# working.net
KiCad netlist of a schematic drawn in EAGLE
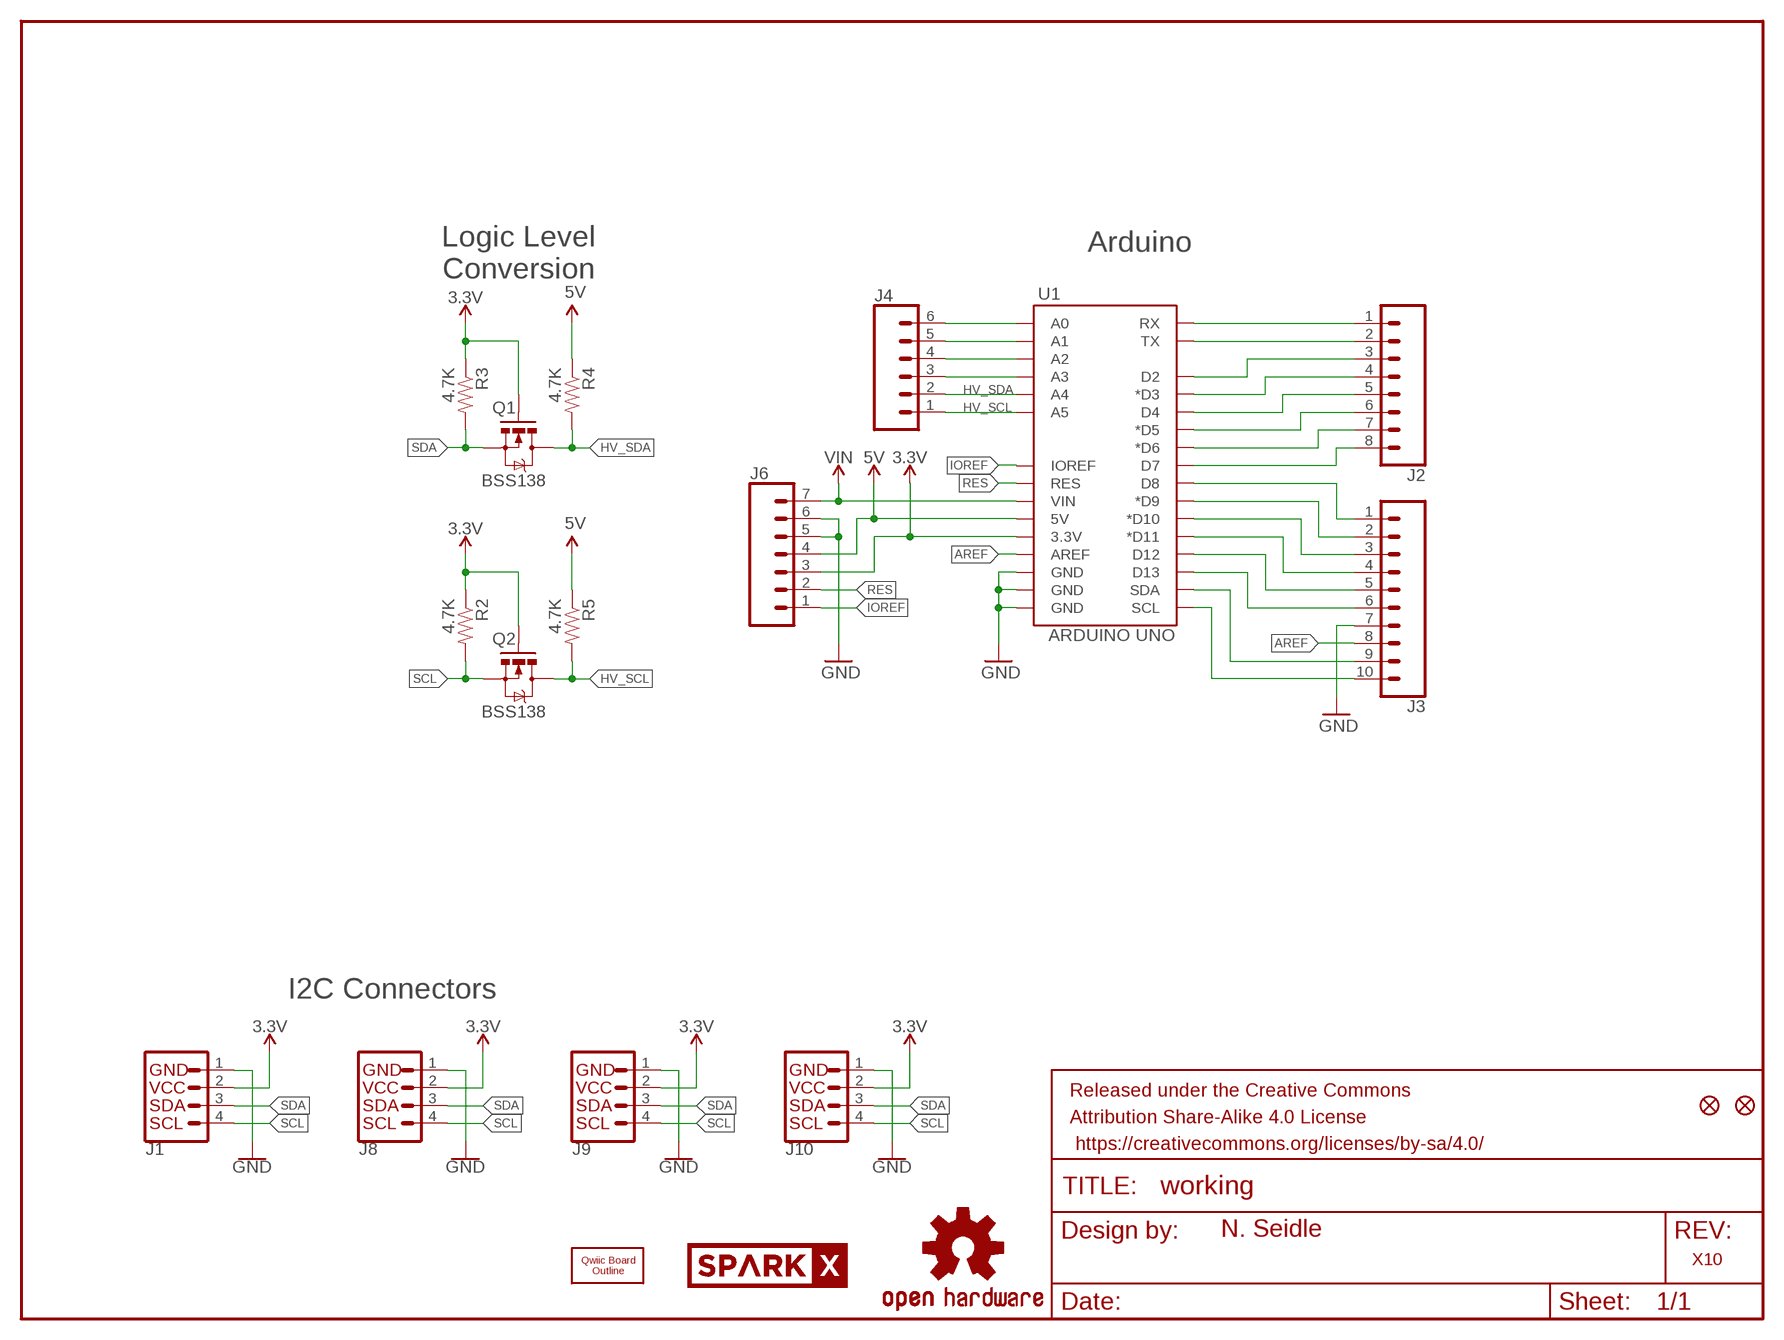
[diagram p0: schematic, sheet 1]

(export (version "E")
  (design (tool "Eeschema 10.0.6"))
  (components
    (comp (ref "FD1")
      (value "FIDUCIAL1X2")
      (footprint "eagle-import:FIDUCIAL-1X2")
      (libsource (lib "eagle-import") (part "FIDUCIAL1X2"))
    )
    (comp (ref "FD2")
      (value "FIDUCIAL1X2")
      (footprint "eagle-import:FIDUCIAL-1X2")
      (libsource (lib "eagle-import") (part "FIDUCIAL1X2"))
    )
    (comp (ref "FRAME1")
      (value "FRAME-LETTER")
      (footprint "eagle-import:CREATIVE_COMMONS")
      (libsource (lib "eagle-import") (part "FRAME-LETTER"))
    )
    (comp (ref "J1")
      (value "I2C_STANDARDJS-1MM")
      (footprint "eagle-import:1X04_1MM_RA")
      (libsource (lib "eagle-import") (part "I2C_STANDARDJS-1MM"))
    )
    (comp (ref "J2")
      (value "CONN_08NO_SILK_FEMALE_PTH")
      (footprint "eagle-import:1X08_NO_SILK")
      (libsource (lib "eagle-import") (part "CONN_08NO_SILK_FEMALE_PTH"))
    )
    (comp (ref "J3")
      (value "CONN_10NO_SILK_PTH_FEMALE")
      (footprint "eagle-import:1X10_NO_SILK")
      (libsource (lib "eagle-import") (part "CONN_10NO_SILK_PTH_FEMALE"))
    )
    (comp (ref "J4")
      (value "CONN_06NO_SILK_FEMALE_PTH")
      (footprint "eagle-import:1X06_NO_SILK")
      (libsource (lib "eagle-import") (part "CONN_06NO_SILK_FEMALE_PTH"))
    )
    (comp (ref "J6")
      (value "CONN_07NO_SILK")
      (footprint "eagle-import:1X07_NO_SILK")
      (libsource (lib "eagle-import") (part "CONN_07NO_SILK"))
    )
    (comp (ref "J8")
      (value "I2C_STANDARDJS-1MM")
      (footprint "eagle-import:1X04_1MM_RA")
      (libsource (lib "eagle-import") (part "I2C_STANDARDJS-1MM"))
    )
    (comp (ref "J9")
      (value "I2C_STANDARDJS-1MM")
      (footprint "eagle-import:1X04_1MM_RA")
      (libsource (lib "eagle-import") (part "I2C_STANDARDJS-1MM"))
    )
    (comp (ref "J10")
      (value "I2C_STANDARDJS-1MM")
      (footprint "eagle-import:1X04_1MM_RA")
      (libsource (lib "eagle-import") (part "I2C_STANDARDJS-1MM"))
    )
    (comp (ref "LOGO1")
      (value "OSHW-LOGOMINI")
      (footprint "eagle-import:OSHW-LOGO-MINI")
      (libsource (lib "eagle-import") (part "OSHW-LOGOMINI"))
    )
    (comp (ref "Q1")
      (value "BSS138")
      (footprint "eagle-import:SOT23-3")
      (libsource (lib "eagle-import") (part "MOSFET-NCHANNELBSS138"))
    )
    (comp (ref "Q2")
      (value "BSS138")
      (footprint "eagle-import:SOT23-3")
      (libsource (lib "eagle-import") (part "MOSFET-NCHANNELBSS138"))
    )
    (comp (ref "R2")
      (value "4.7K")
      (footprint "eagle-import:0603-RES")
      (libsource (lib "eagle-import") (part "4.7KOHM-1/10W-1%(0603)"))
    )
    (comp (ref "R3")
      (value "4.7K")
      (footprint "eagle-import:0603-RES")
      (libsource (lib "eagle-import") (part "4.7KOHM-1/10W-1%(0603)"))
    )
    (comp (ref "R4")
      (value "4.7K")
      (footprint "eagle-import:0603-RES")
      (libsource (lib "eagle-import") (part "4.7KOHM-1/10W-1%(0603)"))
    )
    (comp (ref "R5")
      (value "4.7K")
      (footprint "eagle-import:0603-RES")
      (libsource (lib "eagle-import") (part "4.7KOHM-1/10W-1%(0603)"))
    )
    (comp (ref "U$1")
      (value "SPARKX-LOGO3")
      (footprint "eagle-import:SPARKX-SMALL")
      (libsource (lib "eagle-import") (part "SPARKX-LOGO3"))
    )
    (comp (ref "U$2")
      (value "SPARKX-LOGO5")
      (footprint "eagle-import:SPARKX-LARGE")
      (libsource (lib "eagle-import") (part "SPARKX-LOGO5"))
    )
    (comp (ref "U$3")
      (value "QWIIC_BOARD_OUTLINEH")
      (footprint "eagle-import:QWIIC_BOARD_MOUNT_HOLES")
      (libsource (lib "eagle-import") (part "QWIIC_BOARD_OUTLINEH"))
    )
    (comp (ref "U1")
      (value "ARDUINO UNO")
      (footprint "eagle-import:UNO_R3_SHIELD_NOLABELS")
      (libsource (lib "eagle-import") (part "ARDUINO_R3_SHIELDNOLABELS"))
    )
  )
  (nets
    (net (code "1") (name "3.3V") (class "Default")
      (node (ref "J1") (pin "2") (pinfunction "VCC_2") (pintype "power_in"))
      (node (ref "J10") (pin "2") (pinfunction "VCC_2") (pintype "power_in"))
      (node (ref "J6") (pin "3") (pinfunction "3_3") (pintype "passive"))
      (node (ref "J8") (pin "2") (pinfunction "VCC_2") (pintype "power_in"))
      (node (ref "J9") (pin "2") (pinfunction "VCC_2") (pintype "power_in"))
      (node (ref "Q1") (pin "1") (pinfunction "G_1") (pintype "passive"))
      (node (ref "Q2") (pin "1") (pinfunction "G_1") (pintype "passive"))
      (node (ref "R2") (pin "1") (pinfunction "1_1") (pintype "passive"))
      (node (ref "R3") (pin "1") (pinfunction "1_1") (pintype "passive"))
      (node (ref "U1") (pin "3.3V") (pinfunction "3.3V_3.3V") (pintype "bidirectional"))
    )
    (net (code "2") (name "5V") (class "Default")
      (node (ref "J6") (pin "4") (pinfunction "4_4") (pintype "passive"))
      (node (ref "R4") (pin "1") (pinfunction "1_1") (pintype "passive"))
      (node (ref "R5") (pin "1") (pinfunction "1_1") (pintype "passive"))
      (node (ref "U1") (pin "5V") (pinfunction "5V_5V") (pintype "bidirectional"))
    )
    (net (code "3") (name "AREF") (class "Default")
      (node (ref "J3") (pin "8") (pinfunction "8_8") (pintype "passive"))
      (node (ref "U1") (pin "AREF") (pinfunction "AREF_AREF") (pintype "bidirectional"))
    )
    (net (code "4") (name "GND") (class "Default")
      (node (ref "J1") (pin "1") (pinfunction "GND_1") (pintype "power_in"))
      (node (ref "J10") (pin "1") (pinfunction "GND_1") (pintype "power_in"))
      (node (ref "J3") (pin "7") (pinfunction "7_7") (pintype "passive"))
      (node (ref "J6") (pin "5") (pinfunction "5_5") (pintype "passive"))
      (node (ref "J6") (pin "6") (pinfunction "6_6") (pintype "passive"))
      (node (ref "J8") (pin "1") (pinfunction "GND_1") (pintype "power_in"))
      (node (ref "J9") (pin "1") (pinfunction "GND_1") (pintype "power_in"))
      (node (ref "U1") (pin "GND@0") (pinfunction "GND_GND@0") (pintype "bidirectional"))
      (node (ref "U1") (pin "GND@1") (pinfunction "GND_GND@1") (pintype "bidirectional"))
      (node (ref "U1") (pin "GND@2") (pinfunction "GND_GND@2") (pintype "bidirectional"))
    )
    (net (code "5") (name "HV_SCL") (class "Default")
      (node (ref "J4") (pin "1") (pinfunction "1_1") (pintype "passive"))
      (node (ref "Q2") (pin "3") (pinfunction "D_3") (pintype "passive"))
      (node (ref "R5") (pin "2") (pinfunction "2_2") (pintype "passive"))
      (node (ref "U1") (pin "A5") (pinfunction "A5_A5") (pintype "bidirectional"))
    )
    (net (code "6") (name "HV_SDA") (class "Default")
      (node (ref "J4") (pin "2") (pinfunction "2_2") (pintype "passive"))
      (node (ref "Q1") (pin "3") (pinfunction "D_3") (pintype "passive"))
      (node (ref "R4") (pin "2") (pinfunction "2_2") (pintype "passive"))
      (node (ref "U1") (pin "A4") (pinfunction "A4_A4") (pintype "bidirectional"))
    )
    (net (code "7") (name "IOREF") (class "Default")
      (node (ref "J6") (pin "1") (pinfunction "1_1") (pintype "passive"))
      (node (ref "U1") (pin "IOREF") (pinfunction "IOREF_IOREF") (pintype "bidirectional"))
    )
    (net (code "8") (name "Net-(J2-Pad1)") (class "Default")
      (node (ref "J2") (pin "1") (pinfunction "1_1") (pintype "passive"))
      (node (ref "U1") (pin "RX") (pinfunction "RX_RX") (pintype "bidirectional"))
    )
    (net (code "9") (name "Net-(J2-Pad2)") (class "Default")
      (node (ref "J2") (pin "2") (pinfunction "2_2") (pintype "passive"))
      (node (ref "U1") (pin "TX") (pinfunction "TX_TX") (pintype "bidirectional"))
    )
    (net (code "10") (name "Net-(J2-Pad3)") (class "Default")
      (node (ref "J2") (pin "3") (pinfunction "3_3") (pintype "passive"))
      (node (ref "U1") (pin "D2") (pinfunction "D2_D2") (pintype "bidirectional"))
    )
    (net (code "11") (name "Net-(J2-Pad5)") (class "Default")
      (node (ref "J2") (pin "5") (pinfunction "5_5") (pintype "passive"))
      (node (ref "U1") (pin "D4") (pinfunction "D4_D4") (pintype "bidirectional"))
    )
    (net (code "12") (name "Net-(J2-Pad8)") (class "Default")
      (node (ref "J2") (pin "8") (pinfunction "8_8") (pintype "passive"))
      (node (ref "U1") (pin "D7") (pinfunction "D7_D7") (pintype "bidirectional"))
    )
    (net (code "13") (name "Net-(J3-Pad1)") (class "Default")
      (node (ref "J3") (pin "1") (pinfunction "1_1") (pintype "passive"))
      (node (ref "U1") (pin "D8") (pinfunction "D8_D8") (pintype "bidirectional"))
    )
    (net (code "14") (name "Net-(J3-Pad5)") (class "Default")
      (node (ref "J3") (pin "5") (pinfunction "5_5") (pintype "passive"))
      (node (ref "U1") (pin "D12") (pinfunction "D12_D12") (pintype "bidirectional"))
    )
    (net (code "15") (name "Net-(J3-Pad6)") (class "Default")
      (node (ref "J3") (pin "6") (pinfunction "6_6") (pintype "passive"))
      (node (ref "U1") (pin "D13") (pinfunction "D13_D13") (pintype "bidirectional"))
    )
    (net (code "16") (name "Net-(J3-Pad9)") (class "Default")
      (node (ref "J3") (pin "9") (pinfunction "9_9") (pintype "passive"))
      (node (ref "U1") (pin "SDA") (pinfunction "SDA_SDA") (pintype "bidirectional"))
    )
    (net (code "17") (name "Net-(J3-Pad10)") (class "Default")
      (node (ref "J3") (pin "10") (pinfunction "10_10") (pintype "passive"))
      (node (ref "U1") (pin "SCL") (pinfunction "SCL_SCL") (pintype "bidirectional"))
    )
    (net (code "18") (name "Net-(J4-Pad3)") (class "Default")
      (node (ref "J4") (pin "3") (pinfunction "3_3") (pintype "passive"))
      (node (ref "U1") (pin "A3") (pinfunction "A3_A3") (pintype "bidirectional"))
    )
    (net (code "19") (name "Net-(J4-Pad4)") (class "Default")
      (node (ref "J4") (pin "4") (pinfunction "4_4") (pintype "passive"))
      (node (ref "U1") (pin "A2") (pinfunction "A2_A2") (pintype "bidirectional"))
    )
    (net (code "20") (name "Net-(J4-Pad5)") (class "Default")
      (node (ref "J4") (pin "5") (pinfunction "5_5") (pintype "passive"))
      (node (ref "U1") (pin "A1") (pinfunction "A1_A1") (pintype "bidirectional"))
    )
    (net (code "21") (name "Net-(J4-Pad6)") (class "Default")
      (node (ref "J4") (pin "6") (pinfunction "6_6") (pintype "passive"))
      (node (ref "U1") (pin "A0") (pinfunction "A0_A0") (pintype "bidirectional"))
    )
    (net (code "22") (name "Net-(U1-*D3)") (class "Default")
      (node (ref "J2") (pin "4") (pinfunction "4_4") (pintype "passive"))
      (node (ref "U1") (pin "D3") (pinfunction "*D3_D3") (pintype "bidirectional"))
    )
    (net (code "23") (name "Net-(U1-*D5)") (class "Default")
      (node (ref "J2") (pin "6") (pinfunction "6_6") (pintype "passive"))
      (node (ref "U1") (pin "D5") (pinfunction "*D5_D5") (pintype "bidirectional"))
    )
    (net (code "24") (name "Net-(U1-*D6)") (class "Default")
      (node (ref "J2") (pin "7") (pinfunction "7_7") (pintype "passive"))
      (node (ref "U1") (pin "D6") (pinfunction "*D6_D6") (pintype "bidirectional"))
    )
    (net (code "25") (name "Net-(U1-*D9)") (class "Default")
      (node (ref "J3") (pin "2") (pinfunction "2_2") (pintype "passive"))
      (node (ref "U1") (pin "D9") (pinfunction "*D9_D9") (pintype "bidirectional"))
    )
    (net (code "26") (name "Net-(U1-*D10)") (class "Default")
      (node (ref "J3") (pin "3") (pinfunction "3_3") (pintype "passive"))
      (node (ref "U1") (pin "D10") (pinfunction "*D10_D10") (pintype "bidirectional"))
    )
    (net (code "27") (name "Net-(U1-*D11)") (class "Default")
      (node (ref "J3") (pin "4") (pinfunction "4_4") (pintype "passive"))
      (node (ref "U1") (pin "D11") (pinfunction "*D11_D11") (pintype "bidirectional"))
    )
    (net (code "28") (name "RES") (class "Default")
      (node (ref "J6") (pin "2") (pinfunction "2_2") (pintype "passive"))
      (node (ref "U1") (pin "RES") (pinfunction "RES_RES") (pintype "bidirectional"))
    )
    (net (code "29") (name "SCL") (class "Default")
      (node (ref "J1") (pin "4") (pinfunction "SCL_4") (pintype "passive"))
      (node (ref "J10") (pin "4") (pinfunction "SCL_4") (pintype "passive"))
      (node (ref "J8") (pin "4") (pinfunction "SCL_4") (pintype "passive"))
      (node (ref "J9") (pin "4") (pinfunction "SCL_4") (pintype "passive"))
      (node (ref "Q2") (pin "2") (pinfunction "S_2") (pintype "passive"))
      (node (ref "R2") (pin "2") (pinfunction "2_2") (pintype "passive"))
    )
    (net (code "30") (name "SDA") (class "Default")
      (node (ref "J1") (pin "3") (pinfunction "SDA_3") (pintype "passive"))
      (node (ref "J10") (pin "3") (pinfunction "SDA_3") (pintype "passive"))
      (node (ref "J8") (pin "3") (pinfunction "SDA_3") (pintype "passive"))
      (node (ref "J9") (pin "3") (pinfunction "SDA_3") (pintype "passive"))
      (node (ref "Q1") (pin "2") (pinfunction "S_2") (pintype "passive"))
      (node (ref "R3") (pin "2") (pinfunction "2_2") (pintype "passive"))
    )
    (net (code "31") (name "VIN") (class "Default")
      (node (ref "J6") (pin "7") (pinfunction "7_7") (pintype "passive"))
      (node (ref "U1") (pin "VIN") (pinfunction "VIN_VIN") (pintype "bidirectional"))
    )
  )
)
